# FlowControllerFinal.net
KiCad netlist of a schematic drawn in EAGLE
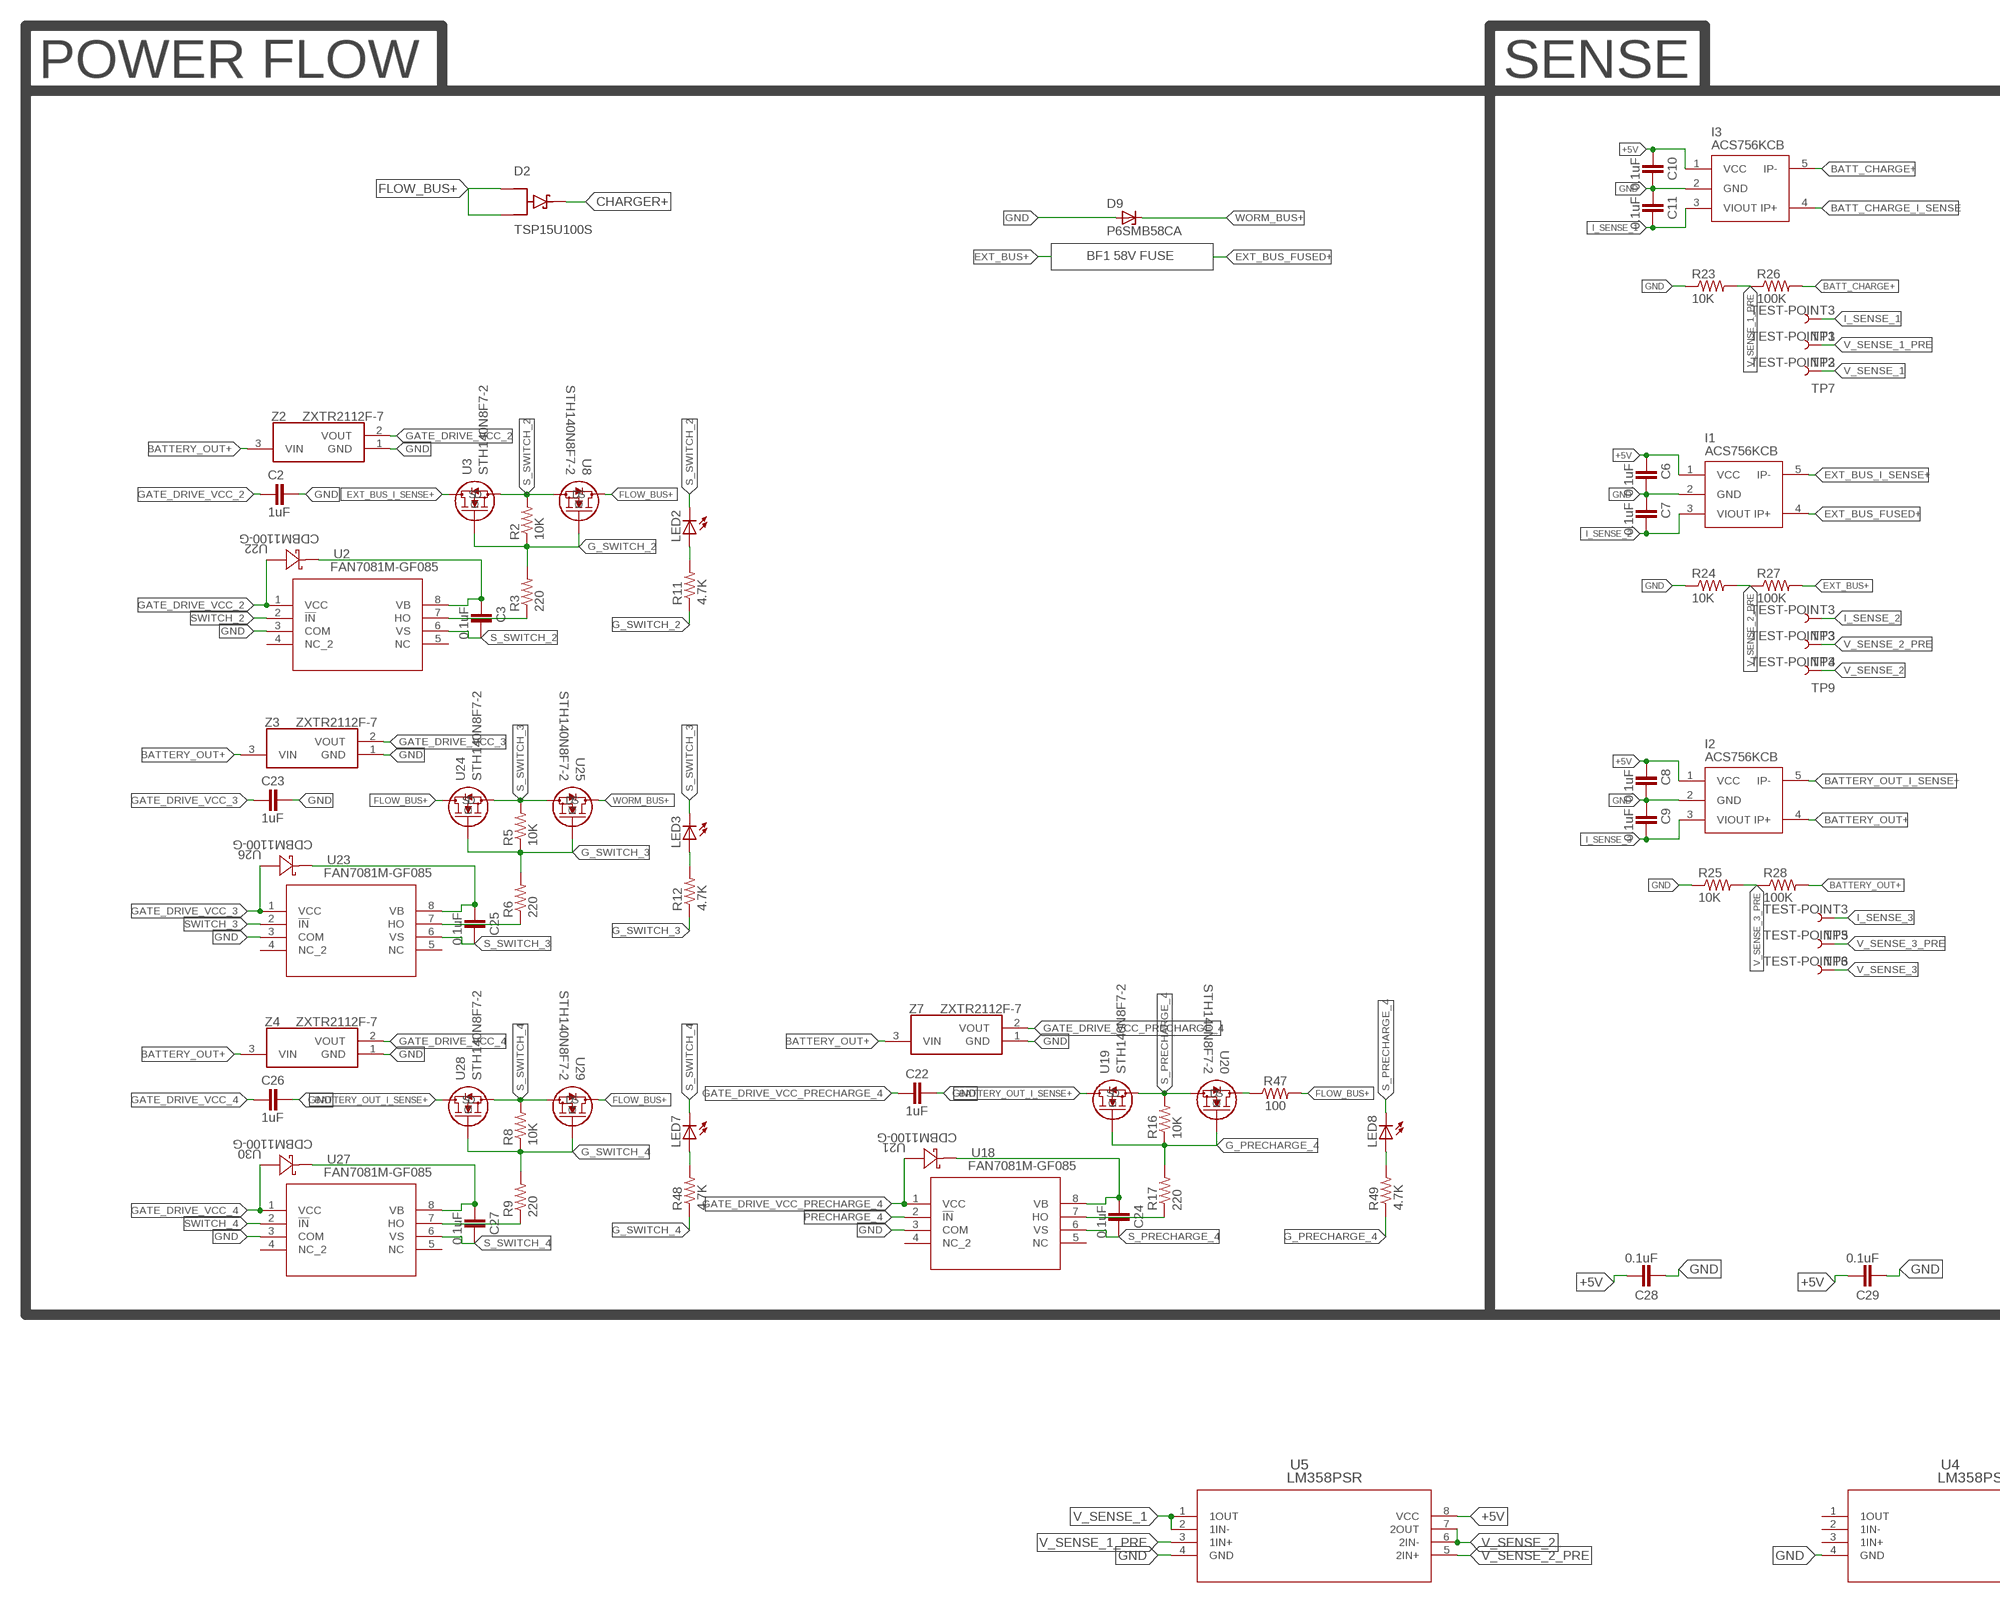
[diagram p0: schematic, sheet 1, part 1 of 2]
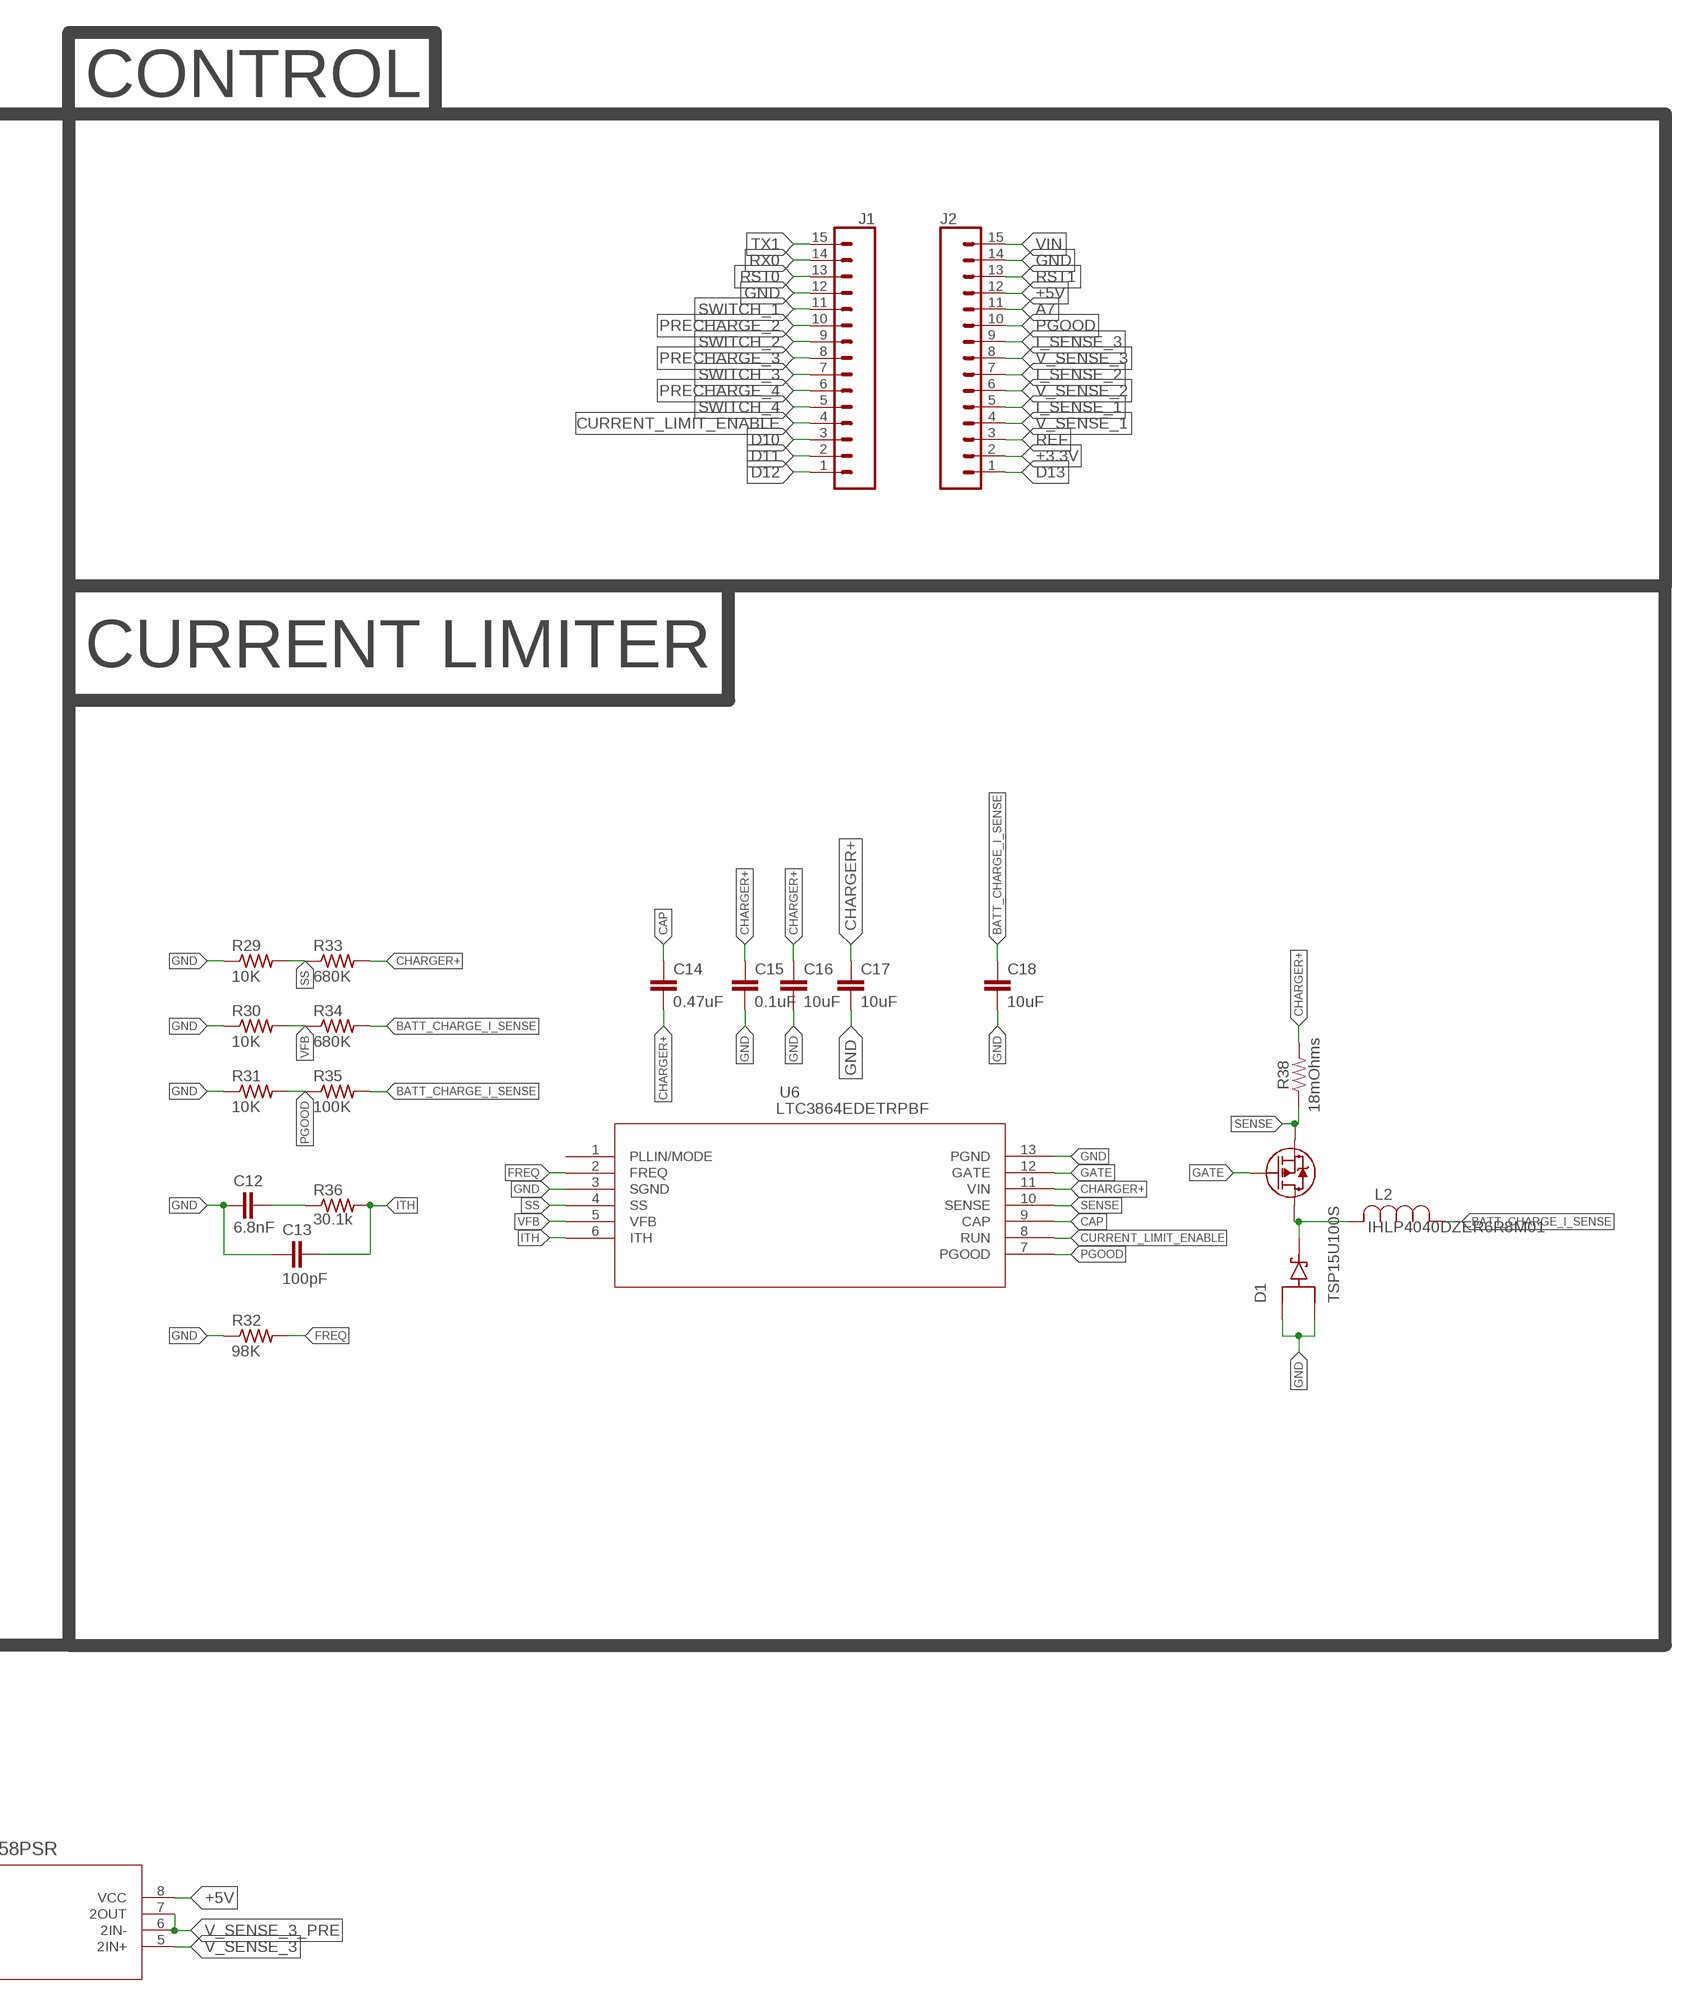
[diagram p1: schematic, sheet 1, part 2 of 2]

(export (version "E")
  (design (tool "Eeschema 10.0.6"))
  (components
    (comp (ref "C2")
      (value "1uF")
      (footprint "eagle-import:0805")
      (libsource (lib "eagle-import") (part "2.2UF-0805-25V-(+80/-20%)"))
    )
    (comp (ref "C3")
      (value "0.1uF")
      (footprint "eagle-import:0805")
      (libsource (lib "eagle-import") (part "2.2UF-0805-25V-(+80/-20%)"))
    )
    (comp (ref "C6")
      (value "0.1uF")
      (footprint "eagle-import:0805")
      (libsource (lib "eagle-import") (part "2.2UF-0805-25V-(+80/-20%)"))
    )
    (comp (ref "C7")
      (value "0.1uF")
      (footprint "eagle-import:0805")
      (libsource (lib "eagle-import") (part "2.2UF-0805-25V-(+80/-20%)"))
    )
    (comp (ref "C8")
      (value "0.1uF")
      (footprint "eagle-import:0805")
      (libsource (lib "eagle-import") (part "2.2UF-0805-25V-(+80/-20%)"))
    )
    (comp (ref "C9")
      (value "0.1uF")
      (footprint "eagle-import:0805")
      (libsource (lib "eagle-import") (part "2.2UF-0805-25V-(+80/-20%)"))
    )
    (comp (ref "C10")
      (value "0.1uF")
      (footprint "eagle-import:0805")
      (libsource (lib "eagle-import") (part "2.2UF-0805-25V-(+80/-20%)"))
    )
    (comp (ref "C11")
      (value "0.1uF")
      (footprint "eagle-import:0805")
      (libsource (lib "eagle-import") (part "2.2UF-0805-25V-(+80/-20%)"))
    )
    (comp (ref "C12")
      (value "6.8nF")
      (footprint "eagle-import:0805")
      (libsource (lib "eagle-import") (part "2.2UF-0805-25V-(+80/-20%)"))
    )
    (comp (ref "C13")
      (value "100pF")
      (footprint "eagle-import:0805")
      (libsource (lib "eagle-import") (part "2.2UF-0805-25V-(+80/-20%)"))
    )
    (comp (ref "C14")
      (value "0.47uF")
      (footprint "eagle-import:0805")
      (libsource (lib "eagle-import") (part "2.2UF-0805-25V-(+80/-20%)"))
    )
    (comp (ref "C15")
      (value "0.1uF")
      (footprint "eagle-import:0805")
      (libsource (lib "eagle-import") (part "2.2UF-0805-25V-(+80/-20%)"))
    )
    (comp (ref "C16")
      (value "10uF")
      (footprint "eagle-import:1210")
      (libsource (lib "eagle-import") (part "10UF-1210-50V-20%"))
    )
    (comp (ref "C17")
      (value "10uF")
      (footprint "eagle-import:1210")
      (libsource (lib "eagle-import") (part "10UF-1210-50V-20%"))
    )
    (comp (ref "C18")
      (value "10uF")
      (footprint "eagle-import:1210")
      (libsource (lib "eagle-import") (part "10UF-1210-50V-20%"))
    )
    (comp (ref "C22")
      (value "1uF")
      (footprint "eagle-import:0805")
      (libsource (lib "eagle-import") (part "2.2UF-0805-25V-(+80/-20%)"))
    )
    (comp (ref "C23")
      (value "1uF")
      (footprint "eagle-import:0805")
      (libsource (lib "eagle-import") (part "2.2UF-0805-25V-(+80/-20%)"))
    )
    (comp (ref "C24")
      (value "0.1uF")
      (footprint "eagle-import:0805")
      (libsource (lib "eagle-import") (part "2.2UF-0805-25V-(+80/-20%)"))
    )
    (comp (ref "C25")
      (value "0.1uF")
      (footprint "eagle-import:0805")
      (libsource (lib "eagle-import") (part "2.2UF-0805-25V-(+80/-20%)"))
    )
    (comp (ref "C26")
      (value "1uF")
      (footprint "eagle-import:0805")
      (libsource (lib "eagle-import") (part "2.2UF-0805-25V-(+80/-20%)"))
    )
    (comp (ref "C27")
      (value "0.1uF")
      (footprint "eagle-import:0805")
      (libsource (lib "eagle-import") (part "2.2UF-0805-25V-(+80/-20%)"))
    )
    (comp (ref "C28")
      (value "0.1uF")
      (footprint "eagle-import:0805")
      (libsource (lib "eagle-import") (part "2.2UF-0805-25V-(+80/-20%)"))
    )
    (comp (ref "C29")
      (value "0.1uF")
      (footprint "eagle-import:0805")
      (libsource (lib "eagle-import") (part "2.2UF-0805-25V-(+80/-20%)"))
    )
    (comp (ref "D1")
      (value "TSP15U100S")
      (footprint "eagle-import:DIO_TSP15U100S")
      (fields
        (field (name "DIGI-KEY_PART_NUMBER") "1801-TSP15U100STR-ND")
        (field (name "MF") "Taiwan Semiconductor")
      )
      (libsource (lib "eagle-import") (part "TSP15U100S"))
    )
    (comp (ref "D2")
      (value "TSP15U100S")
      (footprint "eagle-import:DIO_TSP15U100S")
      (fields
        (field (name "DIGI-KEY_PART_NUMBER") "1801-TSP15U100STR-ND")
        (field (name "MF") "Taiwan Semiconductor")
      )
      (libsource (lib "eagle-import") (part "TSP15U100S"))
    )
    (comp (ref "D9")
      (value "P6SMB58CA")
      (footprint "eagle-import:DO214AA")
      (fields (field (name "MF") "ON Semiconductor") (field (name "MPN") "1SMB5913BT3G"))
      (libsource (lib "eagle-import") (part "1SMB59BT3G13"))
    )
    (comp (ref "I1")
      (value "ACS756KCB")
      (footprint "eagle-import:ACS756KCB")
      (libsource (lib "eagle-import") (part "ACS756KCB"))
    )
    (comp (ref "I2")
      (value "ACS756KCB")
      (footprint "eagle-import:ACS756KCB")
      (libsource (lib "eagle-import") (part "ACS756KCB"))
    )
    (comp (ref "I3")
      (value "ACS756KCB")
      (footprint "eagle-import:ACS756KCB")
      (libsource (lib "eagle-import") (part "ACS756KCB"))
    )
    (comp (ref "J1")
      (value "CONN_15")
      (footprint "eagle-import:1X15")
      (libsource (lib "eagle-import") (part "CONN_15"))
    )
    (comp (ref "J2")
      (value "CONN_15")
      (footprint "eagle-import:1X15")
      (fields (field (name "SPICEPREFIX") "X"))
      (libsource (lib "eagle-import") (part "CONN_15"))
    )
    (comp (ref "L2")
      (value "IHLP4040DZER6R8M01")
      (footprint "eagle-import:IND_IHLP-4040DZ_VIS")
      (fields (field (name "COPYRIGHT") "Copyright (C) 2022 Ultra Librarian. All rights reserved."))
      (libsource (lib "eagle-import") (part "IHLP4040DZER6R8M01"))
    )
    (comp (ref "LED2")
      (value "LEDCHIPLED_0805")
      (footprint "eagle-import:CHIPLED_0805")
      (libsource (lib "eagle-import") (part "LEDCHIPLED_0805"))
    )
    (comp (ref "LED3")
      (value "LEDCHIPLED_0805")
      (footprint "eagle-import:CHIPLED_0805")
      (libsource (lib "eagle-import") (part "LEDCHIPLED_0805"))
    )
    (comp (ref "LED7")
      (value "LEDCHIPLED_0805")
      (footprint "eagle-import:CHIPLED_0805")
      (libsource (lib "eagle-import") (part "LEDCHIPLED_0805"))
    )
    (comp (ref "LED8")
      (value "LEDCHIPLED_0805")
      (footprint "eagle-import:CHIPLED_0805")
      (libsource (lib "eagle-import") (part "LEDCHIPLED_0805"))
    )
    (comp (ref "R2")
      (value "10K")
      (footprint "eagle-import:M0805")
      (libsource (lib "eagle-import") (part "R-US_M0805"))
    )
    (comp (ref "R3")
      (value "220")
      (footprint "eagle-import:M0805")
      (libsource (lib "eagle-import") (part "R-US_M0805"))
    )
    (comp (ref "R5")
      (value "10K")
      (footprint "eagle-import:M0805")
      (libsource (lib "eagle-import") (part "R-US_M0805"))
    )
    (comp (ref "R6")
      (value "220")
      (footprint "eagle-import:M0805")
      (libsource (lib "eagle-import") (part "R-US_M0805"))
    )
    (comp (ref "R8")
      (value "10K")
      (footprint "eagle-import:M0805")
      (libsource (lib "eagle-import") (part "R-US_M0805"))
    )
    (comp (ref "R9")
      (value "220")
      (footprint "eagle-import:M0805")
      (libsource (lib "eagle-import") (part "R-US_M0805"))
    )
    (comp (ref "R11")
      (value "4.7K")
      (footprint "eagle-import:M0805")
      (libsource (lib "eagle-import") (part "R-US_M0805"))
    )
    (comp (ref "R12")
      (value "4.7K")
      (footprint "eagle-import:M0805")
      (libsource (lib "eagle-import") (part "R-US_M0805"))
    )
    (comp (ref "R16")
      (value "10K")
      (footprint "eagle-import:M0805")
      (libsource (lib "eagle-import") (part "R-US_M0805"))
    )
    (comp (ref "R17")
      (value "220")
      (footprint "eagle-import:M0805")
      (libsource (lib "eagle-import") (part "R-US_M0805"))
    )
    (comp (ref "R23")
      (value "10K")
      (footprint "eagle-import:M0805")
      (libsource (lib "eagle-import") (part "R-US_M0805"))
    )
    (comp (ref "R24")
      (value "10K")
      (footprint "eagle-import:M0805")
      (libsource (lib "eagle-import") (part "R-US_M0805"))
    )
    (comp (ref "R25")
      (value "10K")
      (footprint "eagle-import:M0805")
      (libsource (lib "eagle-import") (part "R-US_M0805"))
    )
    (comp (ref "R26")
      (value "100K")
      (footprint "eagle-import:M0805")
      (libsource (lib "eagle-import") (part "R-US_M0805"))
    )
    (comp (ref "R27")
      (value "100K")
      (footprint "eagle-import:M0805")
      (libsource (lib "eagle-import") (part "R-US_M0805"))
    )
    (comp (ref "R28")
      (value "100K")
      (footprint "eagle-import:M0805")
      (libsource (lib "eagle-import") (part "R-US_M0805"))
    )
    (comp (ref "R29")
      (value "10K")
      (footprint "eagle-import:M0805")
      (libsource (lib "eagle-import") (part "R-US_M0805"))
    )
    (comp (ref "R30")
      (value "10K")
      (footprint "eagle-import:M0805")
      (libsource (lib "eagle-import") (part "R-US_M0805"))
    )
    (comp (ref "R31")
      (value "10K")
      (footprint "eagle-import:M0805")
      (libsource (lib "eagle-import") (part "R-US_M0805"))
    )
    (comp (ref "R32")
      (value "98K")
      (footprint "eagle-import:M0805")
      (libsource (lib "eagle-import") (part "R-US_M0805"))
    )
    (comp (ref "R33")
      (value "680K")
      (footprint "eagle-import:M0805")
      (libsource (lib "eagle-import") (part "R-US_M0805"))
    )
    (comp (ref "R34")
      (value "680K")
      (footprint "eagle-import:M0805")
      (libsource (lib "eagle-import") (part "R-US_M0805"))
    )
    (comp (ref "R35")
      (value "100K")
      (footprint "eagle-import:M0805")
      (libsource (lib "eagle-import") (part "R-US_M0805"))
    )
    (comp (ref "R36")
      (value "30.1k")
      (footprint "eagle-import:M0805")
      (libsource (lib "eagle-import") (part "R-US_M0805"))
    )
    (comp (ref "R37")
      (value "RSJ250P10TL")
      (footprint "eagle-import:TRANS_R5009FNJ_ROM")
      (fields (field (name "COPYRIGHT") "Copyright (C) 2022 Ultra Librarian. All rights reserved."))
      (libsource (lib "eagle-import") (part "RSJ250P10TL"))
    )
    (comp (ref "R38")
      (value "18mOhms")
      (footprint "eagle-import:2512")
      (libsource (lib "eagle-import") (part "0.05OHM-2512-3W-1%"))
    )
    (comp (ref "R47")
      (value "100")
      (footprint "eagle-import:2512")
      (libsource (lib "eagle-import") (part "0.05OHM-2512-3W-1%"))
    )
    (comp (ref "R48")
      (value "4.7K")
      (footprint "eagle-import:M0805")
      (libsource (lib "eagle-import") (part "R-US_M0805"))
    )
    (comp (ref "R49")
      (value "4.7K")
      (footprint "eagle-import:M0805")
      (libsource (lib "eagle-import") (part "R-US_M0805"))
    )
    (comp (ref "TP1")
      (value "TEST-POINT3")
      (footprint "eagle-import:PAD.03X.03")
      (libsource (lib "eagle-import") (part "TEST-POINT3"))
    )
    (comp (ref "TP2")
      (value "TEST-POINT3")
      (footprint "eagle-import:PAD.03X.03")
      (libsource (lib "eagle-import") (part "TEST-POINT3"))
    )
    (comp (ref "TP3")
      (value "TEST-POINT3")
      (footprint "eagle-import:PAD.03X.03")
      (libsource (lib "eagle-import") (part "TEST-POINT3"))
    )
    (comp (ref "TP4")
      (value "TEST-POINT3")
      (footprint "eagle-import:PAD.03X.03")
      (libsource (lib "eagle-import") (part "TEST-POINT3"))
    )
    (comp (ref "TP5")
      (value "TEST-POINT3")
      (footprint "eagle-import:PAD.03X.03")
      (libsource (lib "eagle-import") (part "TEST-POINT3"))
    )
    (comp (ref "TP6")
      (value "TEST-POINT3")
      (footprint "eagle-import:PAD.03X.03")
      (libsource (lib "eagle-import") (part "TEST-POINT3"))
    )
    (comp (ref "TP7")
      (value "TEST-POINT3")
      (footprint "eagle-import:PAD.03X.03")
      (libsource (lib "eagle-import") (part "TEST-POINT3"))
    )
    (comp (ref "TP9")
      (value "TEST-POINT3")
      (footprint "eagle-import:PAD.03X.03")
      (libsource (lib "eagle-import") (part "TEST-POINT3"))
    )
    (comp (ref "TP11")
      (value "TEST-POINT3")
      (footprint "eagle-import:PAD.03X.03")
      (libsource (lib "eagle-import") (part "TEST-POINT3"))
    )
    (comp (ref "U2")
      (value "FAN7081M-GF085")
      (footprint "eagle-import:SOIC8_3P9X4P9_ONS")
      (fields (field (name "COPYRIGHT") "Copyright (C) 2022 Ultra Librarian. All rights reserved."))
      (libsource (lib "eagle-import") (part "FAN7081M-GF085"))
    )
    (comp (ref "U3")
      (value "STH140N8F7-2")
      (footprint "eagle-import:HPAK_0N8F7-2_STM")
      (fields (field (name "COPYRIGHT") "Copyright (C) 2022 Ultra Librarian. All rights reserved."))
      (libsource (lib "eagle-import") (part "STH140N8F7-2"))
    )
    (comp (ref "U4")
      (value "LM358PSR")
      (footprint "eagle-import:PS8")
      (fields (field (name "COPYRIGHT") "Copyright (C) 2022 Ultra Librarian. All rights reserved."))
      (libsource (lib "eagle-import") (part "LM358PSR"))
    )
    (comp (ref "U5")
      (value "LM358PSR")
      (footprint "eagle-import:PS8")
      (fields (field (name "COPYRIGHT") "Copyright (C) 2022 Ultra Librarian. All rights reserved."))
      (libsource (lib "eagle-import") (part "LM358PSR"))
    )
    (comp (ref "U6")
      (value "LTC3864EDETRPBF")
      (footprint "eagle-import:DFN-12_DE")
      (fields
        (field (name "DIGI-KEY_PART_NUMBER") "161-LTC3864EDE#TRPBFTR-ND")
        (field (name "MF") "Analog Devices")
        (field (name "MP") "LTC3864EDE#TRPBF")
      )
      (libsource (lib "eagle-import") (part "LTC3864EDETRPBF"))
    )
    (comp (ref "U8")
      (value "STH140N8F7-2")
      (footprint "eagle-import:HPAK_0N8F7-2_STM")
      (fields (field (name "COPYRIGHT") "Copyright (C) 2022 Ultra Librarian. All rights reserved."))
      (libsource (lib "eagle-import") (part "STH140N8F7-2"))
    )
    (comp (ref "U18")
      (value "FAN7081M-GF085")
      (footprint "eagle-import:SOIC8_3P9X4P9_ONS")
      (fields (field (name "COPYRIGHT") "Copyright (C) 2022 Ultra Librarian. All rights reserved."))
      (libsource (lib "eagle-import") (part "FAN7081M-GF085"))
    )
    (comp (ref "U19")
      (value "STH140N8F7-2")
      (footprint "eagle-import:HPAK_0N8F7-2_STM")
      (fields (field (name "COPYRIGHT") "Copyright (C) 2022 Ultra Librarian. All rights reserved."))
      (libsource (lib "eagle-import") (part "STH140N8F7-2"))
    )
    (comp (ref "U20")
      (value "STH140N8F7-2")
      (footprint "eagle-import:HPAK_0N8F7-2_STM")
      (fields (field (name "COPYRIGHT") "Copyright (C) 2022 Ultra Librarian. All rights reserved."))
      (libsource (lib "eagle-import") (part "STH140N8F7-2"))
    )
    (comp (ref "U21")
      (value "CDBM1100-G")
      (footprint "eagle-import:CDBM")
      (fields (field (name "COPYRIGHT") "Copyright (C) 2022 Ultra Librarian. All rights reserved."))
      (libsource (lib "eagle-import") (part "CDBM1100-G"))
    )
    (comp (ref "U22")
      (value "CDBM1100-G")
      (footprint "eagle-import:CDBM")
      (fields (field (name "COPYRIGHT") "Copyright (C) 2022 Ultra Librarian. All rights reserved."))
      (libsource (lib "eagle-import") (part "CDBM1100-G"))
    )
    (comp (ref "U23")
      (value "FAN7081M-GF085")
      (footprint "eagle-import:SOIC8_3P9X4P9_ONS")
      (fields (field (name "COPYRIGHT") "Copyright (C) 2022 Ultra Librarian. All rights reserved."))
      (libsource (lib "eagle-import") (part "FAN7081M-GF085"))
    )
    (comp (ref "U24")
      (value "STH140N8F7-2")
      (footprint "eagle-import:HPAK_0N8F7-2_STM")
      (fields (field (name "COPYRIGHT") "Copyright (C) 2022 Ultra Librarian. All rights reserved."))
      (libsource (lib "eagle-import") (part "STH140N8F7-2"))
    )
    (comp (ref "U25")
      (value "STH140N8F7-2")
      (footprint "eagle-import:HPAK_0N8F7-2_STM")
      (fields (field (name "COPYRIGHT") "Copyright (C) 2022 Ultra Librarian. All rights reserved."))
      (libsource (lib "eagle-import") (part "STH140N8F7-2"))
    )
    (comp (ref "U26")
      (value "CDBM1100-G")
      (footprint "eagle-import:CDBM")
      (fields (field (name "COPYRIGHT") "Copyright (C) 2022 Ultra Librarian. All rights reserved."))
      (libsource (lib "eagle-import") (part "CDBM1100-G"))
    )
    (comp (ref "U27")
      (value "FAN7081M-GF085")
      (footprint "eagle-import:SOIC8_3P9X4P9_ONS")
      (fields (field (name "COPYRIGHT") "Copyright (C) 2022 Ultra Librarian. All rights reserved."))
      (libsource (lib "eagle-import") (part "FAN7081M-GF085"))
    )
    (comp (ref "U28")
      (value "STH140N8F7-2")
      (footprint "eagle-import:HPAK_0N8F7-2_STM")
      (fields (field (name "COPYRIGHT") "Copyright (C) 2022 Ultra Librarian. All rights reserved."))
      (libsource (lib "eagle-import") (part "STH140N8F7-2"))
    )
    (comp (ref "U29")
      (value "STH140N8F7-2")
      (footprint "eagle-import:HPAK_0N8F7-2_STM")
      (fields (field (name "COPYRIGHT") "Copyright (C) 2022 Ultra Librarian. All rights reserved."))
      (libsource (lib "eagle-import") (part "STH140N8F7-2"))
    )
    (comp (ref "U30")
      (value "CDBM1100-G")
      (footprint "eagle-import:CDBM")
      (fields (field (name "COPYRIGHT") "Copyright (C) 2022 Ultra Librarian. All rights reserved."))
      (libsource (lib "eagle-import") (part "CDBM1100-G"))
    )
    (comp (ref "Z2")
      (value "ZXTR2112F-7")
      (footprint "eagle-import:SOT96P240X110-3N")
      (fields (field (name "MOUSER_PART_NUMBER") "621-ZXTR2112F-7"))
      (libsource (lib "eagle-import") (part "ZXTR2112F-7"))
    )
    (comp (ref "Z3")
      (value "ZXTR2112F-7")
      (footprint "eagle-import:SOT96P240X110-3N")
      (fields (field (name "MOUSER_PART_NUMBER") "621-ZXTR2112F-7"))
      (libsource (lib "eagle-import") (part "ZXTR2112F-7"))
    )
    (comp (ref "Z4")
      (value "ZXTR2112F-7")
      (footprint "eagle-import:SOT96P240X110-3N")
      (fields (field (name "MOUSER_PART_NUMBER") "621-ZXTR2112F-7"))
      (libsource (lib "eagle-import") (part "ZXTR2112F-7"))
    )
    (comp (ref "Z7")
      (value "ZXTR2112F-7")
      (footprint "eagle-import:SOT96P240X110-3N")
      (fields (field (name "MOUSER_PART_NUMBER") "621-ZXTR2112F-7"))
      (libsource (lib "eagle-import") (part "ZXTR2112F-7"))
    )
  )
  (nets
    (net (code "1") (name "+3.3V") (class "Default")
      (node (ref "J2") (pin "2") (pinfunction "2_2") (pintype "passive"))
    )
    (net (code "2") (name "+5V") (class "Default")
      (node (ref "C10") (pin "1") (pinfunction "1_1") (pintype "passive"))
      (node (ref "C28") (pin "2") (pinfunction "2_2") (pintype "passive"))
      (node (ref "C29") (pin "2") (pinfunction "2_2") (pintype "passive"))
      (node (ref "C6") (pin "1") (pinfunction "1_1") (pintype "passive"))
      (node (ref "C8") (pin "1") (pinfunction "1_1") (pintype "passive"))
      (node (ref "I1") (pin "1") (pinfunction "VCC_1") (pintype "bidirectional"))
      (node (ref "I2") (pin "1") (pinfunction "VCC_1") (pintype "bidirectional"))
      (node (ref "I3") (pin "1") (pinfunction "VCC_1") (pintype "bidirectional"))
      (node (ref "J2") (pin "12") (pinfunction "12_12") (pintype "passive"))
      (node (ref "U4") (pin "8") (pinfunction "VCC_8") (pintype "power_in"))
      (node (ref "U5") (pin "8") (pinfunction "VCC_8") (pintype "power_in"))
    )
    (net (code "3") (name "A7") (class "Default")
      (node (ref "J2") (pin "11") (pinfunction "11_11") (pintype "passive"))
    )
    (net (code "4") (name "BATTERY_OUT+") (class "Default")
      (node (ref "I2") (pin "4") (pinfunction "IP+_4") (pintype "bidirectional"))
      (node (ref "R28") (pin "2") (pinfunction "2_2") (pintype "passive"))
      (node (ref "Z2") (pin "3") (pinfunction "VIN_3") (pintype "bidirectional"))
      (node (ref "Z3") (pin "3") (pinfunction "VIN_3") (pintype "bidirectional"))
      (node (ref "Z4") (pin "3") (pinfunction "VIN_3") (pintype "bidirectional"))
      (node (ref "Z7") (pin "3") (pinfunction "VIN_3") (pintype "bidirectional"))
    )
    (net (code "5") (name "BATTERY_OUT_I_SENSE+") (class "Default")
      (node (ref "I2") (pin "5") (pinfunction "IP-_5") (pintype "bidirectional"))
      (node (ref "U19") (pin "2") (pinfunction "D_2") (pintype "passive"))
      (node (ref "U28") (pin "2") (pinfunction "D_2") (pintype "passive"))
    )
    (net (code "6") (name "BATT_CHARGE+") (class "Default")
      (node (ref "I3") (pin "5") (pinfunction "IP-_5") (pintype "bidirectional"))
      (node (ref "R26") (pin "2") (pinfunction "2_2") (pintype "passive"))
    )
    (net (code "7") (name "BATT_CHARGE_I_SENSE") (class "Default")
      (node (ref "C18") (pin "1") (pinfunction "1_1") (pintype "passive"))
      (node (ref "I3") (pin "4") (pinfunction "IP+_4") (pintype "bidirectional"))
      (node (ref "L2") (pin "1") (pinfunction "1_1") (pintype "passive"))
      (node (ref "R34") (pin "2") (pinfunction "2_2") (pintype "passive"))
      (node (ref "R35") (pin "2") (pinfunction "2_2") (pintype "passive"))
    )
    (net (code "8") (name "CAP") (class "Default")
      (node (ref "C14") (pin "1") (pinfunction "1_1") (pintype "passive"))
      (node (ref "U6") (pin "9") (pinfunction "CAP_9") (pintype "passive"))
    )
    (net (code "9") (name "CHARGER+") (class "Default")
      (node (ref "C14") (pin "2") (pinfunction "2_2") (pintype "passive"))
      (node (ref "C15") (pin "1") (pinfunction "1_1") (pintype "passive"))
      (node (ref "C16") (pin "1") (pinfunction "1_1") (pintype "passive"))
      (node (ref "C17") (pin "1") (pinfunction "1_1") (pintype "passive"))
      (node (ref "D2") (pin "3") (pinfunction "K_3") (pintype "passive"))
      (node (ref "R33") (pin "2") (pinfunction "2_2") (pintype "passive"))
      (node (ref "R38") (pin "P$2") (pinfunction "2_P$2") (pintype "passive"))
      (node (ref "U6") (pin "11") (pinfunction "VIN_11") (pintype "input"))
    )
    (net (code "10") (name "CURRENT_LIMIT_ENABLE") (class "Default")
      (node (ref "J1") (pin "4") (pinfunction "4_4") (pintype "passive"))
      (node (ref "U6") (pin "8") (pinfunction "RUN_8") (pintype "input"))
    )
    (net (code "11") (name "D10") (class "Default")
      (node (ref "J1") (pin "3") (pinfunction "3_3") (pintype "passive"))
    )
    (net (code "12") (name "D11") (class "Default")
      (node (ref "J1") (pin "2") (pinfunction "2_2") (pintype "passive"))
    )
    (net (code "13") (name "D12") (class "Default")
      (node (ref "J1") (pin "1") (pinfunction "1_1") (pintype "passive"))
    )
    (net (code "14") (name "D13") (class "Default")
      (node (ref "J2") (pin "1") (pinfunction "1_1") (pintype "passive"))
    )
    (net (code "15") (name "EXT_BUS+") (class "Default")
      (node (ref "R27") (pin "2") (pinfunction "2_2") (pintype "passive"))
    )
    (net (code "16") (name "EXT_BUS_FUSED+") (class "Default")
      (node (ref "I1") (pin "4") (pinfunction "IP+_4") (pintype "bidirectional"))
    )
    (net (code "17") (name "EXT_BUS_I_SENSE+") (class "Default")
      (node (ref "I1") (pin "5") (pinfunction "IP-_5") (pintype "bidirectional"))
      (node (ref "U3") (pin "2") (pinfunction "D_2") (pintype "passive"))
    )
    (net (code "18") (name "FLOW_BUS+") (class "Default")
      (node (ref "D2") (pin "1") (pinfunction "A1_1") (pintype "passive"))
      (node (ref "D2") (pin "2") (pinfunction "A2_2") (pintype "passive"))
      (node (ref "R47") (pin "P$2") (pinfunction "2_P$2") (pintype "passive"))
      (node (ref "U24") (pin "2") (pinfunction "D_2") (pintype "passive"))
      (node (ref "U29") (pin "2") (pinfunction "D_2") (pintype "passive"))
      (node (ref "U8") (pin "2") (pinfunction "D_2") (pintype "passive"))
    )
    (net (code "19") (name "FREQ") (class "Default")
      (node (ref "R32") (pin "2") (pinfunction "2_2") (pintype "passive"))
      (node (ref "U6") (pin "2") (pinfunction "FREQ_2") (pintype "input"))
    )
    (net (code "20") (name "GATE") (class "Default")
      (node (ref "R37") (pin "1") (pinfunction "1_1") (pintype "passive"))
      (node (ref "U6") (pin "12") (pinfunction "GATE_12") (pintype "output"))
    )
    (net (code "21") (name "GATE_DRIVE_VCC_2") (class "Default")
      (node (ref "C2") (pin "1") (pinfunction "1_1") (pintype "passive"))
      (node (ref "U2") (pin "1") (pinfunction "VCC_1") (pintype "power_in"))
      (node (ref "U22") (pin "2") (pinfunction "2_2") (pintype "passive"))
      (node (ref "Z2") (pin "2") (pinfunction "VOUT_2") (pintype "bidirectional"))
    )
    (net (code "22") (name "GATE_DRIVE_VCC_3") (class "Default")
      (node (ref "C23") (pin "1") (pinfunction "1_1") (pintype "passive"))
      (node (ref "U23") (pin "1") (pinfunction "VCC_1") (pintype "power_in"))
      (node (ref "U26") (pin "2") (pinfunction "2_2") (pintype "passive"))
      (node (ref "Z3") (pin "2") (pinfunction "VOUT_2") (pintype "bidirectional"))
    )
    (net (code "23") (name "GATE_DRIVE_VCC_4") (class "Default")
      (node (ref "C26") (pin "1") (pinfunction "1_1") (pintype "passive"))
      (node (ref "U27") (pin "1") (pinfunction "VCC_1") (pintype "power_in"))
      (node (ref "U30") (pin "2") (pinfunction "2_2") (pintype "passive"))
      (node (ref "Z4") (pin "2") (pinfunction "VOUT_2") (pintype "bidirectional"))
    )
    (net (code "24") (name "GATE_DRIVE_VCC_PRECHARGE_4") (class "Default")
      (node (ref "C22") (pin "1") (pinfunction "1_1") (pintype "passive"))
      (node (ref "U18") (pin "1") (pinfunction "VCC_1") (pintype "power_in"))
      (node (ref "U21") (pin "2") (pinfunction "2_2") (pintype "passive"))
      (node (ref "Z7") (pin "2") (pinfunction "VOUT_2") (pintype "bidirectional"))
    )
    (net (code "25") (name "GND") (class "Default")
      (node (ref "C10") (pin "2") (pinfunction "2_2") (pintype "passive"))
      (node (ref "C11") (pin "1") (pinfunction "1_1") (pintype "passive"))
      (node (ref "C12") (pin "1") (pinfunction "1_1") (pintype "passive"))
      (node (ref "C13") (pin "1") (pinfunction "1_1") (pintype "passive"))
      (node (ref "C15") (pin "2") (pinfunction "2_2") (pintype "passive"))
      (node (ref "C16") (pin "2") (pinfunction "2_2") (pintype "passive"))
      (node (ref "C17") (pin "2") (pinfunction "2_2") (pintype "passive"))
      (node (ref "C18") (pin "2") (pinfunction "2_2") (pintype "passive"))
      (node (ref "C2") (pin "2") (pinfunction "2_2") (pintype "passive"))
      (node (ref "C22") (pin "2") (pinfunction "2_2") (pintype "passive"))
      (node (ref "C23") (pin "2") (pinfunction "2_2") (pintype "passive"))
      (node (ref "C26") (pin "2") (pinfunction "2_2") (pintype "passive"))
      (node (ref "C28") (pin "1") (pinfunction "1_1") (pintype "passive"))
      (node (ref "C29") (pin "1") (pinfunction "1_1") (pintype "passive"))
      (node (ref "C6") (pin "2") (pinfunction "2_2") (pintype "passive"))
      (node (ref "C7") (pin "1") (pinfunction "1_1") (pintype "passive"))
      (node (ref "C8") (pin "2") (pinfunction "2_2") (pintype "passive"))
      (node (ref "C9") (pin "1") (pinfunction "1_1") (pintype "passive"))
      (node (ref "D1") (pin "1") (pinfunction "A1_1") (pintype "passive"))
      (node (ref "D1") (pin "2") (pinfunction "A2_2") (pintype "passive"))
      (node (ref "D9") (pin "A") (pinfunction "A_A") (pintype "passive"))
      (node (ref "I1") (pin "2") (pinfunction "GND_2") (pintype "bidirectional"))
      (node (ref "I2") (pin "2") (pinfunction "GND_2") (pintype "bidirectional"))
      (node (ref "I3") (pin "2") (pinfunction "GND_2") (pintype "bidirectional"))
      (node (ref "J1") (pin "12") (pinfunction "12_12") (pintype "passive"))
      (node (ref "J2") (pin "14") (pinfunction "14_14") (pintype "passive"))
      (node (ref "R23") (pin "1") (pinfunction "1_1") (pintype "passive"))
      (node (ref "R24") (pin "1") (pinfunction "1_1") (pintype "passive"))
      (node (ref "R25") (pin "1") (pinfunction "1_1") (pintype "passive"))
      (node (ref "R29") (pin "1") (pinfunction "1_1") (pintype "passive"))
      (node (ref "R30") (pin "1") (pinfunction "1_1") (pintype "passive"))
      (node (ref "R31") (pin "1") (pinfunction "1_1") (pintype "passive"))
      (node (ref "R32") (pin "1") (pinfunction "1_1") (pintype "passive"))
      (node (ref "U18") (pin "3") (pinfunction "COM_3") (pintype "passive"))
      (node (ref "U2") (pin "3") (pinfunction "COM_3") (pintype "passive"))
      (node (ref "U23") (pin "3") (pinfunction "COM_3") (pintype "passive"))
      (node (ref "U27") (pin "3") (pinfunction "COM_3") (pintype "passive"))
      (node (ref "U4") (pin "4") (pinfunction "GND_4") (pintype "power_in"))
      (node (ref "U5") (pin "4") (pinfunction "GND_4") (pintype "power_in"))
      (node (ref "U6") (pin "13") (pinfunction "PGND_13") (pintype "power_in"))
      (node (ref "U6") (pin "3") (pinfunction "SGND_3") (pintype "power_in"))
      (node (ref "Z2") (pin "1") (pinfunction "GND_1") (pintype "bidirectional"))
      (node (ref "Z3") (pin "1") (pinfunction "GND_1") (pintype "bidirectional"))
      (node (ref "Z4") (pin "1") (pinfunction "GND_1") (pintype "bidirectional"))
      (node (ref "Z7") (pin "1") (pinfunction "GND_1") (pintype "bidirectional"))
    )
    (net (code "26") (name "G_PRECHARGE_4") (class "Default")
      (node (ref "R16") (pin "1") (pinfunction "1_1") (pintype "passive"))
      (node (ref "R17") (pin "2") (pinfunction "2_2") (pintype "passive"))
      (node (ref "R49") (pin "1") (pinfunction "1_1") (pintype "passive"))
      (node (ref "U19") (pin "1") (pinfunction "G_1") (pintype "passive"))
      (node (ref "U20") (pin "1") (pinfunction "G_1") (pintype "passive"))
    )
    (net (code "27") (name "G_SWITCH_2") (class "Default")
      (node (ref "R11") (pin "1") (pinfunction "1_1") (pintype "passive"))
      (node (ref "R2") (pin "1") (pinfunction "1_1") (pintype "passive"))
      (node (ref "R3") (pin "2") (pinfunction "2_2") (pintype "passive"))
      (node (ref "U3") (pin "1") (pinfunction "G_1") (pintype "passive"))
      (node (ref "U8") (pin "1") (pinfunction "G_1") (pintype "passive"))
    )
    (net (code "28") (name "G_SWITCH_3") (class "Default")
      (node (ref "R12") (pin "1") (pinfunction "1_1") (pintype "passive"))
      (node (ref "R5") (pin "1") (pinfunction "1_1") (pintype "passive"))
      (node (ref "R6") (pin "2") (pinfunction "2_2") (pintype "passive"))
      (node (ref "U24") (pin "1") (pinfunction "G_1") (pintype "passive"))
      (node (ref "U25") (pin "1") (pinfunction "G_1") (pintype "passive"))
    )
    (net (code "29") (name "G_SWITCH_4") (class "Default")
      (node (ref "R48") (pin "1") (pinfunction "1_1") (pintype "passive"))
      (node (ref "R8") (pin "1") (pinfunction "1_1") (pintype "passive"))
      (node (ref "R9") (pin "2") (pinfunction "2_2") (pintype "passive"))
      (node (ref "U28") (pin "1") (pinfunction "G_1") (pintype "passive"))
      (node (ref "U29") (pin "1") (pinfunction "G_1") (pintype "passive"))
    )
    (net (code "30") (name "ITH") (class "Default")
      (node (ref "C13") (pin "2") (pinfunction "2_2") (pintype "passive"))
      (node (ref "R36") (pin "2") (pinfunction "2_2") (pintype "passive"))
      (node (ref "U6") (pin "6") (pinfunction "ITH_6") (pintype "output"))
    )
    (net (code "31") (name "I_SENSE_1") (class "Default")
      (node (ref "C11") (pin "2") (pinfunction "2_2") (pintype "passive"))
      (node (ref "I3") (pin "3") (pinfunction "VIOUT_3") (pintype "bidirectional"))
      (node (ref "J2") (pin "5") (pinfunction "5_5") (pintype "passive"))
      (node (ref "TP1") (pin "P$1") (pinfunction "1_P$1") (pintype "bidirectional"))
    )
    (net (code "32") (name "I_SENSE_2") (class "Default")
      (node (ref "C7") (pin "2") (pinfunction "2_2") (pintype "passive"))
      (node (ref "I1") (pin "3") (pinfunction "VIOUT_3") (pintype "bidirectional"))
      (node (ref "J2") (pin "7") (pinfunction "7_7") (pintype "passive"))
      (node (ref "TP3") (pin "P$1") (pinfunction "1_P$1") (pintype "bidirectional"))
    )
    (net (code "33") (name "I_SENSE_3") (class "Default")
      (node (ref "C9") (pin "2") (pinfunction "2_2") (pintype "passive"))
      (node (ref "I2") (pin "3") (pinfunction "VIOUT_3") (pintype "bidirectional"))
      (node (ref "J2") (pin "9") (pinfunction "9_9") (pintype "passive"))
      (node (ref "TP5") (pin "P$1") (pinfunction "1_P$1") (pintype "bidirectional"))
    )
    (net (code "34") (name "Net-(C12-Pad2)") (class "Default")
      (node (ref "C12") (pin "2") (pinfunction "2_2") (pintype "passive"))
      (node (ref "R36") (pin "1") (pinfunction "1_1") (pintype "passive"))
    )
    (net (code "35") (name "Net-(D1-K)") (class "Default")
      (node (ref "D1") (pin "3") (pinfunction "K_3") (pintype "passive"))
      (node (ref "L2") (pin "2") (pinfunction "2_2") (pintype "passive"))
      (node (ref "R37") (pin "2") (pinfunction "3_2") (pintype "passive"))
    )
    (net (code "36") (name "Net-(LED2-PadA)") (class "Default")
      (node (ref "LED2") (pin "A") (pinfunction "A_A") (pintype "passive"))
      (node (ref "R11") (pin "2") (pinfunction "2_2") (pintype "passive"))
    )
    (net (code "37") (name "Net-(LED3-PadA)") (class "Default")
      (node (ref "LED3") (pin "A") (pinfunction "A_A") (pintype "passive"))
      (node (ref "R12") (pin "2") (pinfunction "2_2") (pintype "passive"))
    )
    (net (code "38") (name "Net-(LED7-PadA)") (class "Default")
      (node (ref "LED7") (pin "A") (pinfunction "A_A") (pintype "passive"))
      (node (ref "R48") (pin "2") (pinfunction "2_2") (pintype "passive"))
    )
    (net (code "39") (name "Net-(LED8-PadA)") (class "Default")
      (node (ref "LED8") (pin "A") (pinfunction "A_A") (pintype "passive"))
      (node (ref "R49") (pin "2") (pinfunction "2_2") (pintype "passive"))
    )
    (net (code "40") (name "Net-(R47-1)") (class "Default")
      (node (ref "R47") (pin "P$1") (pinfunction "1_P$1") (pintype "passive"))
      (node (ref "U20") (pin "2") (pinfunction "D_2") (pintype "passive"))
    )
    (net (code "41") (name "Net-(U2-HO)") (class "Default")
      (node (ref "R3") (pin "1") (pinfunction "1_1") (pintype "passive"))
      (node (ref "U2") (pin "7") (pinfunction "HO_7") (pintype "output"))
    )
    (net (code "42") (name "Net-(U2-VB)") (class "Default")
      (node (ref "C3") (pin "1") (pinfunction "1_1") (pintype "passive"))
      (node (ref "U2") (pin "8") (pinfunction "VB_8") (pintype "power_in"))
      (node (ref "U22") (pin "1") (pinfunction "1_1") (pintype "passive"))
    )
    (net (code "43") (name "Net-(U18-HO)") (class "Default")
      (node (ref "R17") (pin "1") (pinfunction "1_1") (pintype "passive"))
      (node (ref "U18") (pin "7") (pinfunction "HO_7") (pintype "output"))
    )
    (net (code "44") (name "Net-(U18-VB)") (class "Default")
      (node (ref "C24") (pin "1") (pinfunction "1_1") (pintype "passive"))
      (node (ref "U18") (pin "8") (pinfunction "VB_8") (pintype "power_in"))
      (node (ref "U21") (pin "1") (pinfunction "1_1") (pintype "passive"))
    )
    (net (code "45") (name "Net-(U23-HO)") (class "Default")
      (node (ref "R6") (pin "1") (pinfunction "1_1") (pintype "passive"))
      (node (ref "U23") (pin "7") (pinfunction "HO_7") (pintype "output"))
    )
    (net (code "46") (name "Net-(U23-VB)") (class "Default")
      (node (ref "C25") (pin "1") (pinfunction "1_1") (pintype "passive"))
      (node (ref "U23") (pin "8") (pinfunction "VB_8") (pintype "power_in"))
      (node (ref "U26") (pin "1") (pinfunction "1_1") (pintype "passive"))
    )
    (net (code "47") (name "Net-(U27-HO)") (class "Default")
      (node (ref "R9") (pin "1") (pinfunction "1_1") (pintype "passive"))
      (node (ref "U27") (pin "7") (pinfunction "HO_7") (pintype "output"))
    )
    (net (code "48") (name "Net-(U27-VB)") (class "Default")
      (node (ref "C27") (pin "1") (pinfunction "1_1") (pintype "passive"))
      (node (ref "U27") (pin "8") (pinfunction "VB_8") (pintype "power_in"))
      (node (ref "U30") (pin "1") (pinfunction "1_1") (pintype "passive"))
    )
    (net (code "49") (name "PGOOD") (class "Default")
      (node (ref "J2") (pin "10") (pinfunction "10_10") (pintype "passive"))
      (node (ref "R31") (pin "2") (pinfunction "2_2") (pintype "passive"))
      (node (ref "R35") (pin "1") (pinfunction "1_1") (pintype "passive"))
      (node (ref "U6") (pin "7") (pinfunction "PGOOD_7") (pintype "output"))
    )
    (net (code "50") (name "PRECHARGE_2") (class "Default")
      (node (ref "J1") (pin "10") (pinfunction "10_10") (pintype "passive"))
    )
    (net (code "51") (name "PRECHARGE_3") (class "Default")
      (node (ref "J1") (pin "8") (pinfunction "8_8") (pintype "passive"))
    )
    (net (code "52") (name "PRECHARGE_4") (class "Default")
      (node (ref "J1") (pin "6") (pinfunction "6_6") (pintype "passive"))
      (node (ref "U18") (pin "2") (pinfunction "~{IN}_2") (pintype "input"))
    )
    (net (code "53") (name "REF") (class "Default")
      (node (ref "J2") (pin "3") (pinfunction "3_3") (pintype "passive"))
    )
    (net (code "54") (name "RST0") (class "Default")
      (node (ref "J1") (pin "13") (pinfunction "13_13") (pintype "passive"))
    )
    (net (code "55") (name "RST1") (class "Default")
      (node (ref "J2") (pin "13") (pinfunction "13_13") (pintype "passive"))
    )
    (net (code "56") (name "RX0") (class "Default")
      (node (ref "J1") (pin "14") (pinfunction "14_14") (pintype "passive"))
    )
    (net (code "57") (name "SENSE") (class "Default")
      (node (ref "R37") (pin "3") (pinfunction "2_3") (pintype "passive"))
      (node (ref "R38") (pin "P$1") (pinfunction "1_P$1") (pintype "passive"))
      (node (ref "U6") (pin "10") (pinfunction "SENSE_10") (pintype "input"))
    )
    (net (code "58") (name "SS") (class "Default")
      (node (ref "R29") (pin "2") (pinfunction "2_2") (pintype "passive"))
      (node (ref "R33") (pin "1") (pinfunction "1_1") (pintype "passive"))
      (node (ref "U6") (pin "4") (pinfunction "SS_4") (pintype "input"))
    )
    (net (code "59") (name "SWITCH_1") (class "Default")
      (node (ref "J1") (pin "11") (pinfunction "11_11") (pintype "passive"))
    )
    (net (code "60") (name "SWITCH_2") (class "Default")
      (node (ref "J1") (pin "9") (pinfunction "9_9") (pintype "passive"))
      (node (ref "U2") (pin "2") (pinfunction "~{IN}_2") (pintype "input"))
    )
    (net (code "61") (name "SWITCH_3") (class "Default")
      (node (ref "J1") (pin "7") (pinfunction "7_7") (pintype "passive"))
      (node (ref "U23") (pin "2") (pinfunction "~{IN}_2") (pintype "input"))
    )
    (net (code "62") (name "SWITCH_4") (class "Default")
      (node (ref "J1") (pin "5") (pinfunction "5_5") (pintype "passive"))
      (node (ref "U27") (pin "2") (pinfunction "~{IN}_2") (pintype "input"))
    )
    (net (code "63") (name "S_PRECHARGE_4") (class "Default")
      (node (ref "C24") (pin "2") (pinfunction "2_2") (pintype "passive"))
      (node (ref "LED8") (pin "C") (pinfunction "C_C") (pintype "passive"))
      (node (ref "R16") (pin "2") (pinfunction "2_2") (pintype "passive"))
      (node (ref "U18") (pin "6") (pinfunction "VS_6") (pintype "power_in"))
      (node (ref "U19") (pin "3") (pinfunction "S_3") (pintype "passive"))
      (node (ref "U20") (pin "3") (pinfunction "S_3") (pintype "passive"))
    )
    (net (code "64") (name "S_SWITCH_2") (class "Default")
      (node (ref "C3") (pin "2") (pinfunction "2_2") (pintype "passive"))
      (node (ref "LED2") (pin "C") (pinfunction "C_C") (pintype "passive"))
      (node (ref "R2") (pin "2") (pinfunction "2_2") (pintype "passive"))
      (node (ref "U2") (pin "6") (pinfunction "VS_6") (pintype "power_in"))
      (node (ref "U3") (pin "3") (pinfunction "S_3") (pintype "passive"))
      (node (ref "U8") (pin "3") (pinfunction "S_3") (pintype "passive"))
    )
    (net (code "65") (name "S_SWITCH_3") (class "Default")
      (node (ref "C25") (pin "2") (pinfunction "2_2") (pintype "passive"))
      (node (ref "LED3") (pin "C") (pinfunction "C_C") (pintype "passive"))
      (node (ref "R5") (pin "2") (pinfunction "2_2") (pintype "passive"))
      (node (ref "U23") (pin "6") (pinfunction "VS_6") (pintype "power_in"))
      (node (ref "U24") (pin "3") (pinfunction "S_3") (pintype "passive"))
      (node (ref "U25") (pin "3") (pinfunction "S_3") (pintype "passive"))
    )
    (net (code "66") (name "S_SWITCH_4") (class "Default")
      (node (ref "C27") (pin "2") (pinfunction "2_2") (pintype "passive"))
      (node (ref "LED7") (pin "C") (pinfunction "C_C") (pintype "passive"))
      (node (ref "R8") (pin "2") (pinfunction "2_2") (pintype "passive"))
      (node (ref "U27") (pin "6") (pinfunction "VS_6") (pintype "power_in"))
      (node (ref "U28") (pin "3") (pinfunction "S_3") (pintype "passive"))
      (node (ref "U29") (pin "3") (pinfunction "S_3") (pintype "passive"))
    )
    (net (code "67") (name "TX1") (class "Default")
      (node (ref "J1") (pin "15") (pinfunction "15_15") (pintype "passive"))
    )
    (net (code "68") (name "VFB") (class "Default")
      (node (ref "R30") (pin "2") (pinfunction "2_2") (pintype "passive"))
      (node (ref "R34") (pin "1") (pinfunction "1_1") (pintype "passive"))
      (node (ref "U6") (pin "5") (pinfunction "VFB_5") (pintype "output"))
    )
    (net (code "69") (name "VIN") (class "Default")
      (node (ref "J2") (pin "15") (pinfunction "15_15") (pintype "passive"))
    )
    (net (code "70") (name "V_SENSE_1") (class "Default")
      (node (ref "J2") (pin "4") (pinfunction "4_4") (pintype "passive"))
      (node (ref "TP7") (pin "P$1") (pinfunction "1_P$1") (pintype "bidirectional"))
      (node (ref "U5") (pin "1") (pinfunction "1OUT_1") (pintype "output"))
      (node (ref "U5") (pin "2") (pinfunction "1IN-_2") (pintype "input"))
    )
    (net (code "71") (name "V_SENSE_1_PRE") (class "Default")
      (node (ref "R23") (pin "2") (pinfunction "2_2") (pintype "passive"))
      (node (ref "R26") (pin "1") (pinfunction "1_1") (pintype "passive"))
      (node (ref "TP2") (pin "P$1") (pinfunction "1_P$1") (pintype "bidirectional"))
      (node (ref "U5") (pin "3") (pinfunction "1IN+_3") (pintype "input"))
    )
    (net (code "72") (name "V_SENSE_2") (class "Default")
      (node (ref "J2") (pin "6") (pinfunction "6_6") (pintype "passive"))
      (node (ref "TP9") (pin "P$1") (pinfunction "1_P$1") (pintype "bidirectional"))
      (node (ref "U5") (pin "6") (pinfunction "2IN-_6") (pintype "input"))
      (node (ref "U5") (pin "7") (pinfunction "2OUT_7") (pintype "output"))
    )
    (net (code "73") (name "V_SENSE_2_PRE") (class "Default")
      (node (ref "R24") (pin "2") (pinfunction "2_2") (pintype "passive"))
      (node (ref "R27") (pin "1") (pinfunction "1_1") (pintype "passive"))
      (node (ref "TP4") (pin "P$1") (pinfunction "1_P$1") (pintype "bidirectional"))
      (node (ref "U5") (pin "5") (pinfunction "2IN+_5") (pintype "input"))
    )
    (net (code "74") (name "V_SENSE_3") (class "Default")
      (node (ref "J2") (pin "8") (pinfunction "8_8") (pintype "passive"))
      (node (ref "TP11") (pin "P$1") (pinfunction "1_P$1") (pintype "bidirectional"))
      (node (ref "U4") (pin "5") (pinfunction "2IN+_5") (pintype "input"))
    )
    (net (code "75") (name "V_SENSE_3_PRE") (class "Default")
      (node (ref "R25") (pin "2") (pinfunction "2_2") (pintype "passive"))
      (node (ref "R28") (pin "1") (pinfunction "1_1") (pintype "passive"))
      (node (ref "TP6") (pin "P$1") (pinfunction "1_P$1") (pintype "bidirectional"))
      (node (ref "U4") (pin "6") (pinfunction "2IN-_6") (pintype "input"))
      (node (ref "U4") (pin "7") (pinfunction "2OUT_7") (pintype "output"))
    )
    (net (code "76") (name "WORM_BUS+") (class "Default")
      (node (ref "D9") (pin "C") (pinfunction "C_C") (pintype "passive"))
      (node (ref "U25") (pin "2") (pinfunction "D_2") (pintype "passive"))
    )
    (net (code "77") (name "unconnected-(U2-NC-Pad5)") (class "Default")
      (node (ref "U2") (pin "5") (pinfunction "NC_5") (pintype "no_connect"))
    )
    (net (code "78") (name "unconnected-(U2-NC_2-Pad4)") (class "Default")
      (node (ref "U2") (pin "4") (pinfunction "NC_2_4") (pintype "no_connect"))
    )
    (net (code "79") (name "unconnected-(U4-1IN+-Pad3)") (class "Default")
      (node (ref "U4") (pin "3") (pinfunction "1IN+_3") (pintype "input"))
    )
    (net (code "80") (name "unconnected-(U4-1IN--Pad2)") (class "Default")
      (node (ref "U4") (pin "2") (pinfunction "1IN-_2") (pintype "input"))
    )
    (net (code "81") (name "unconnected-(U4-1OUT-Pad1)") (class "Default")
      (node (ref "U4") (pin "1") (pinfunction "1OUT_1") (pintype "output"))
    )
    (net (code "82") (name "unconnected-(U6-PLLIN{slash}MODE-Pad1)") (class "Default")
      (node (ref "U6") (pin "1") (pinfunction "PLLIN/MODE_1") (pintype "input"))
    )
    (net (code "83") (name "unconnected-(U18-NC-Pad5)") (class "Default")
      (node (ref "U18") (pin "5") (pinfunction "NC_5") (pintype "no_connect"))
    )
    (net (code "84") (name "unconnected-(U18-NC_2-Pad4)") (class "Default")
      (node (ref "U18") (pin "4") (pinfunction "NC_2_4") (pintype "no_connect"))
    )
    (net (code "85") (name "unconnected-(U23-NC-Pad5)") (class "Default")
      (node (ref "U23") (pin "5") (pinfunction "NC_5") (pintype "no_connect"))
    )
    (net (code "86") (name "unconnected-(U23-NC_2-Pad4)") (class "Default")
      (node (ref "U23") (pin "4") (pinfunction "NC_2_4") (pintype "no_connect"))
    )
    (net (code "87") (name "unconnected-(U27-NC-Pad5)") (class "Default")
      (node (ref "U27") (pin "5") (pinfunction "NC_5") (pintype "no_connect"))
    )
    (net (code "88") (name "unconnected-(U27-NC_2-Pad4)") (class "Default")
      (node (ref "U27") (pin "4") (pinfunction "NC_2_4") (pintype "no_connect"))
    )
  )
)
